# MOTHER.net
KiCad netlist of a schematic drawn in Altium Designer
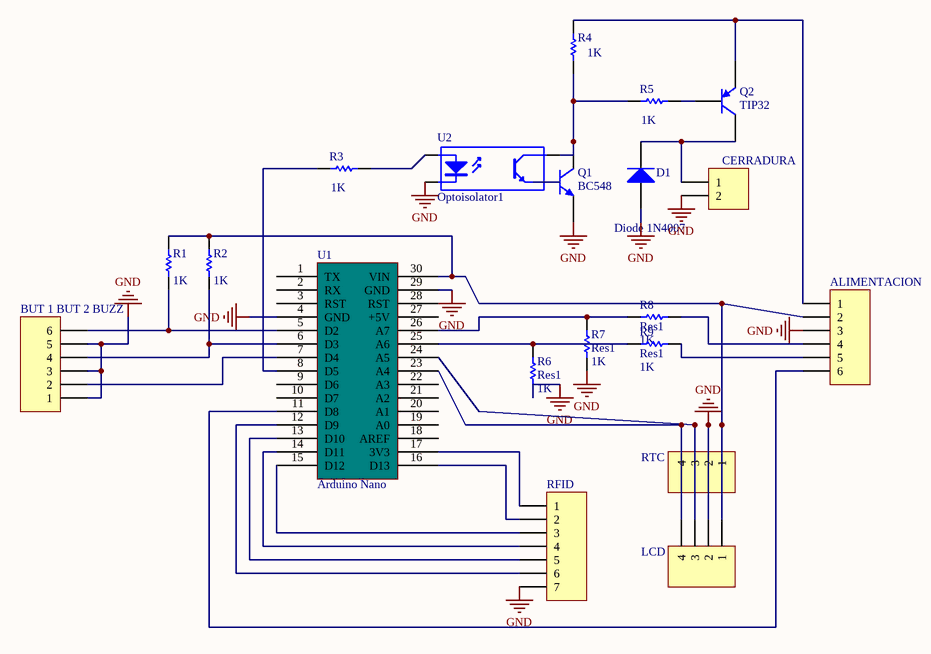
[diagram p0: MOTHER.SchDoc]

(export (version "E")
  (design (tool "Eeschema 10.0.6"))
  (components
    (comp (ref "ALIMENTACION")
      (value "Header 6")
      (footprint "BORNERA 6 PIN")
      (description "Header, 6-Pin")
      (fields (field (name "PUBLISHER") "Altium Limited"))
      (libsource (lib "") (part "Header 6_1"))
    )
    (comp (ref "BUT 1 BUT 2 BUZZ")
      (value "Header 6")
      (footprint "BORNERA 6 PIN")
      (description "Header, 6-Pin")
      (fields (field (name "PUBLISHER") "Altium Limited"))
      (libsource (lib "Miscellaneous Connectors") (part "Header 6"))
    )
    (comp (ref "CERRADURA")
      (value "Header 2")
      (footprint "Bornera 2 pin")
      (description "Header, 2-Pin")
      (fields (field (name "PUBLISHER") "Altium Limited"))
      (libsource (lib "Miscellaneous Connectors") (part "Header 2"))
    )
    (comp (ref "D1")
      (value "Diode 1N4007")
      (footprint "DO-41")
      (description "1 Amp General Purpose Rectifier")
      (fields (field (name "PUBLISHER") "Altium Limited"))
      (libsource (lib "Miscellaneous Devices") (part "Diode 1N4007"))
    )
    (comp (ref "LCD")
      (value "Header 4")
      (footprint "BORNERA 4 PIN")
      (description "Header, 4-Pin")
      (fields (field (name "PUBLISHER") "Altium Limited"))
      (libsource (lib "Miscellaneous Connectors") (part "Header 4"))
    )
    (comp (ref "Q1")
      (value "BC548")
      (footprint "TO-92A")
      (description "NPN General Purpose Amplifier")
      (fields (field (name "PUBLISHER") "Altium Limited"))
      (libsource (lib "Miscellaneous Devices") (part "2N3904"))
    )
    (comp (ref "Q2")
      (value "TIP32")
      (footprint "TO-220AB")
      (description "PNP General Purpose Amplifier")
      (fields (field (name "PUBLISHER") "Altium Limited"))
      (libsource (lib "Miscellaneous Devices") (part "2N3906"))
    )
    (comp (ref "R1")
      (value "1K")
      (footprint "AXIAL-0.3")
      (description "Resistor")
      (fields (field (name "Comment") "Res1") (field (name "PUBLISHER") "Altium Limited"))
      (libsource (lib "Miscellaneous Devices") (part "Res1"))
    )
    (comp (ref "R2")
      (value "1K")
      (footprint "AXIAL-0.3")
      (description "Resistor")
      (fields (field (name "Comment") "Res1") (field (name "PUBLISHER") "Altium Limited"))
      (libsource (lib "Miscellaneous Devices") (part "Res1"))
    )
    (comp (ref "R3")
      (value "1K")
      (footprint "AXIAL-0.3")
      (description "Resistor")
      (fields (field (name "Comment") "Res1") (field (name "PUBLISHER") "Altium Limited"))
      (libsource (lib "Miscellaneous Devices") (part "Res1"))
    )
    (comp (ref "R4")
      (value "1K")
      (footprint "AXIAL-0.3")
      (description "Resistor")
      (fields (field (name "Comment") "Res1") (field (name "PUBLISHER") "Altium Limited"))
      (libsource (lib "Miscellaneous Devices") (part "Res1"))
    )
    (comp (ref "R5")
      (value "1K")
      (footprint "AXIAL-0.3")
      (description "Resistor")
      (fields (field (name "Comment") "Res1") (field (name "PUBLISHER") "Altium Limited"))
      (libsource (lib "Miscellaneous Devices") (part "Res1"))
    )
    (comp (ref "R6")
      (value "Res1")
      (footprint "AXIAL-0.3")
      (description "Resistor")
      (fields (field (name "ALTIUM_VALUE") "1K") (field (name "PUBLISHER") "Altium Limited"))
      (libsource (lib "Miscellaneous Devices") (part "Res1"))
    )
    (comp (ref "R7")
      (value "Res1")
      (footprint "AXIAL-0.3")
      (description "Resistor")
      (fields (field (name "ALTIUM_VALUE") "1K") (field (name "PUBLISHER") "Altium Limited"))
      (libsource (lib "Miscellaneous Devices") (part "Res1"))
    )
    (comp (ref "R8")
      (value "Res1")
      (footprint "AXIAL-0.3")
      (description "Resistor")
      (fields (field (name "ALTIUM_VALUE") "1K") (field (name "PUBLISHER") "Altium Limited"))
      (libsource (lib "Miscellaneous Devices") (part "Res1"))
    )
    (comp (ref "R9")
      (value "Res1")
      (footprint "AXIAL-0.3")
      (description "Resistor")
      (fields (field (name "ALTIUM_VALUE") "1K") (field (name "PUBLISHER") "Altium Limited"))
      (libsource (lib "Miscellaneous Devices") (part "Res1"))
    )
    (comp (ref "RFID")
      (value "Header 7")
      (footprint "BORNERA 7 PIN")
      (description "Header, 7-Pin")
      (fields (field (name "PUBLISHER") "Altium Limited"))
      (libsource (lib "Miscellaneous Connectors") (part "Header 7"))
    )
    (comp (ref "RTC")
      (value "Header 4")
      (footprint "BORNERA 4 PIN")
      (description "Header, 4-Pin")
      (fields (field (name "PUBLISHER") "Altium Limited"))
      (libsource (lib "Miscellaneous Connectors") (part "Header 4"))
    )
    (comp (ref "U1")
      (value "Arduino Nano")
      (footprint "Arduino nano")
      (libsource (lib "Nano") (part "Component_1"))
    )
    (comp (ref "U2")
      (value "Optoisolator1")
      (footprint "DIP-6")
      (description "4-Pin Phototransistor Optocoupler")
      (fields (field (name "PUBLISHER") "Altium Limited"))
      (libsource (lib "Miscellaneous Devices") (part "Optoisolator1"))
    )
  )
  (nets
    (net (code "1") (name "GND") (class "Default")
      (node (ref "ALIMENTACION") (pin "3") (pinfunction "3_3") (pintype "passive"))
      (node (ref "BUT 1 BUT 2 BUZZ") (pin "1") (pinfunction "1_1") (pintype "passive"))
      (node (ref "BUT 1 BUT 2 BUZZ") (pin "3") (pinfunction "3_3") (pintype "passive"))
      (node (ref "BUT 1 BUT 2 BUZZ") (pin "5") (pinfunction "5_5") (pintype "passive"))
      (node (ref "CERRADURA") (pin "2") (pinfunction "2_2") (pintype "passive"))
      (node (ref "D1") (pin "1") (pinfunction "A_1") (pintype "passive"))
      (node (ref "LCD") (pin "2") (pinfunction "2_2") (pintype "passive"))
      (node (ref "Q1") (pin "1") (pinfunction "E_1") (pintype "passive"))
      (node (ref "R6") (pin "1") (pinfunction "1_1") (pintype "passive"))
      (node (ref "R7") (pin "1") (pinfunction "1_1") (pintype "passive"))
      (node (ref "RFID") (pin "7") (pinfunction "7_7") (pintype "passive"))
      (node (ref "RTC") (pin "2") (pinfunction "2_2") (pintype "passive"))
      (node (ref "U1") (pin "29") (pinfunction "GND_29") (pintype "passive"))
      (node (ref "U1") (pin "4") (pinfunction "GND_4") (pintype "passive"))
      (node (ref "U2") (pin "2") (pinfunction "K_2") (pintype "passive"))
    )
    (net (code "2") (name "Net-(ALIMENTACION-Pad4)") (class "Default")
      (node (ref "ALIMENTACION") (pin "4") (pinfunction "4_4") (pintype "passive"))
      (node (ref "R8") (pin "2") (pinfunction "2_2") (pintype "passive"))
    )
    (net (code "3") (name "Net-(ALIMENTACION-Pad5)") (class "Default")
      (node (ref "ALIMENTACION") (pin "5") (pinfunction "5_5") (pintype "passive"))
      (node (ref "R9") (pin "2") (pinfunction "2_2") (pintype "passive"))
    )
    (net (code "4") (name "Net-(D1-K)") (class "Default")
      (node (ref "CERRADURA") (pin "1") (pinfunction "1_1") (pintype "passive"))
      (node (ref "D1") (pin "2") (pinfunction "K_2") (pintype "passive"))
      (node (ref "Q2") (pin "3") (pinfunction "C_3") (pintype "passive"))
    )
    (net (code "5") (name "Net-(Q1-B)") (class "Default")
      (node (ref "Q1") (pin "2") (pinfunction "B_2") (pintype "passive"))
      (node (ref "U2") (pin "3") (pinfunction "E_3") (pintype "passive"))
    )
    (net (code "6") (name "Net-(Q1-C)") (class "Default")
      (node (ref "Q1") (pin "3") (pinfunction "C_3") (pintype "passive"))
      (node (ref "R4") (pin "1") (pinfunction "1_1") (pintype "passive"))
      (node (ref "R5") (pin "1") (pinfunction "1_1") (pintype "passive"))
      (node (ref "U2") (pin "4") (pinfunction "C_4") (pintype "passive"))
    )
    (net (code "7") (name "Net-(Q2-B)") (class "Default")
      (node (ref "Q2") (pin "2") (pinfunction "B_2") (pintype "passive"))
      (node (ref "R5") (pin "2") (pinfunction "2_2") (pintype "passive"))
    )
    (net (code "8") (name "Net-(Q2-E)") (class "Default")
      (node (ref "ALIMENTACION") (pin "1") (pinfunction "1_1") (pintype "passive"))
      (node (ref "Q2") (pin "1") (pinfunction "E_1") (pintype "passive"))
      (node (ref "R4") (pin "2") (pinfunction "2_2") (pintype "passive"))
    )
    (net (code "9") (name "Net-(U1-3V3)") (class "Default")
      (node (ref "RFID") (pin "1") (pinfunction "1_1") (pintype "passive"))
      (node (ref "U1") (pin "17") (pinfunction "3V3_17") (pintype "passive"))
    )
    (net (code "10") (name "Net-(U1-A4)") (class "Default")
      (node (ref "LCD") (pin "4") (pinfunction "4_4") (pintype "passive"))
      (node (ref "RTC") (pin "4") (pinfunction "4_4") (pintype "passive"))
      (node (ref "U1") (pin "23") (pinfunction "A4_23") (pintype "passive"))
    )
    (net (code "11") (name "Net-(U1-A5)") (class "Default")
      (node (ref "LCD") (pin "3") (pinfunction "3_3") (pintype "passive"))
      (node (ref "RTC") (pin "3") (pinfunction "3_3") (pintype "passive"))
      (node (ref "U1") (pin "24") (pinfunction "A5_24") (pintype "passive"))
    )
    (net (code "12") (name "Net-(U1-A6)") (class "Default")
      (node (ref "R6") (pin "2") (pinfunction "2_2") (pintype "passive"))
      (node (ref "R9") (pin "1") (pinfunction "1_1") (pintype "passive"))
      (node (ref "U1") (pin "25") (pinfunction "A6_25") (pintype "passive"))
    )
    (net (code "13") (name "Net-(U1-A7)") (class "Default")
      (node (ref "R7") (pin "2") (pinfunction "2_2") (pintype "passive"))
      (node (ref "R8") (pin "1") (pinfunction "1_1") (pintype "passive"))
      (node (ref "U1") (pin "26") (pinfunction "A7_26") (pintype "passive"))
    )
    (net (code "14") (name "Net-(U1-D2)") (class "Default")
      (node (ref "BUT 1 BUT 2 BUZZ") (pin "6") (pinfunction "6_6") (pintype "passive"))
      (node (ref "R1") (pin "1") (pinfunction "1_1") (pintype "passive"))
      (node (ref "U1") (pin "5") (pinfunction "D2_5") (pintype "passive"))
    )
    (net (code "15") (name "Net-(U1-D3)") (class "Default")
      (node (ref "BUT 1 BUT 2 BUZZ") (pin "4") (pinfunction "4_4") (pintype "passive"))
      (node (ref "R2") (pin "1") (pinfunction "1_1") (pintype "passive"))
      (node (ref "U1") (pin "6") (pinfunction "D3_6") (pintype "passive"))
    )
    (net (code "16") (name "Net-(U1-D4)") (class "Default")
      (node (ref "BUT 1 BUT 2 BUZZ") (pin "2") (pinfunction "2_2") (pintype "passive"))
      (node (ref "U1") (pin "7") (pinfunction "D4_7") (pintype "passive"))
    )
    (net (code "17") (name "Net-(U1-D5)") (class "Default")
      (node (ref "R3") (pin "1") (pinfunction "1_1") (pintype "passive"))
      (node (ref "U1") (pin "8") (pinfunction "D5_8") (pintype "passive"))
    )
    (net (code "18") (name "Net-(U1-D8)") (class "Default")
      (node (ref "ALIMENTACION") (pin "6") (pinfunction "6_6") (pintype "passive"))
      (node (ref "U1") (pin "11") (pinfunction "D8_11") (pintype "passive"))
    )
    (net (code "19") (name "Net-(U1-D9)") (class "Default")
      (node (ref "RFID") (pin "6") (pinfunction "6_6") (pintype "passive"))
      (node (ref "U1") (pin "12") (pinfunction "D9_12") (pintype "passive"))
    )
    (net (code "20") (name "Net-(U1-D10)") (class "Default")
      (node (ref "RFID") (pin "5") (pinfunction "5_5") (pintype "passive"))
      (node (ref "U1") (pin "13") (pinfunction "D10_13") (pintype "passive"))
    )
    (net (code "21") (name "Net-(U1-D11)") (class "Default")
      (node (ref "RFID") (pin "4") (pinfunction "4_4") (pintype "passive"))
      (node (ref "U1") (pin "14") (pinfunction "D11_14") (pintype "passive"))
    )
    (net (code "22") (name "Net-(U1-D12)") (class "Default")
      (node (ref "RFID") (pin "3") (pinfunction "3_3") (pintype "passive"))
      (node (ref "U1") (pin "15") (pinfunction "D12_15") (pintype "passive"))
    )
    (net (code "23") (name "Net-(U1-D13)") (class "Default")
      (node (ref "RFID") (pin "2") (pinfunction "2_2") (pintype "passive"))
      (node (ref "U1") (pin "16") (pinfunction "D13_16") (pintype "passive"))
    )
    (net (code "24") (name "Net-(U1-VIN)") (class "Default")
      (node (ref "ALIMENTACION") (pin "2") (pinfunction "2_2") (pintype "passive"))
      (node (ref "LCD") (pin "1") (pinfunction "1_1") (pintype "passive"))
      (node (ref "R1") (pin "2") (pinfunction "2_2") (pintype "passive"))
      (node (ref "R2") (pin "2") (pinfunction "2_2") (pintype "passive"))
      (node (ref "RTC") (pin "1") (pinfunction "1_1") (pintype "passive"))
      (node (ref "U1") (pin "30") (pinfunction "VIN_30") (pintype "passive"))
    )
    (net (code "25") (name "Net-(U2-A)") (class "Default")
      (node (ref "R3") (pin "2") (pinfunction "2_2") (pintype "passive"))
      (node (ref "U2") (pin "1") (pinfunction "A_1") (pintype "passive"))
    )
    (net (code "26") (name "unconnected-(U1-+5V-Pad27)") (class "Default")
      (node (ref "U1") (pin "27") (pinfunction "+5V_27") (pintype "passive"))
    )
    (net (code "27") (name "unconnected-(U1-A0-Pad19)") (class "Default")
      (node (ref "U1") (pin "19") (pinfunction "A0_19") (pintype "passive"))
    )
    (net (code "28") (name "unconnected-(U1-A1-Pad20)") (class "Default")
      (node (ref "U1") (pin "20") (pinfunction "A1_20") (pintype "passive"))
    )
    (net (code "29") (name "unconnected-(U1-A2-Pad21)") (class "Default")
      (node (ref "U1") (pin "21") (pinfunction "A2_21") (pintype "passive"))
    )
    (net (code "30") (name "unconnected-(U1-A3-Pad22)") (class "Default")
      (node (ref "U1") (pin "22") (pinfunction "A3_22") (pintype "passive"))
    )
    (net (code "31") (name "unconnected-(U1-AREF-Pad18)") (class "Default")
      (node (ref "U1") (pin "18") (pinfunction "AREF_18") (pintype "passive"))
    )
    (net (code "32") (name "unconnected-(U1-D6-Pad9)") (class "Default")
      (node (ref "U1") (pin "9") (pinfunction "D6_9") (pintype "passive"))
    )
    (net (code "33") (name "unconnected-(U1-D7-Pad10)") (class "Default")
      (node (ref "U1") (pin "10") (pinfunction "D7_10") (pintype "passive"))
    )
    (net (code "34") (name "unconnected-(U1-RST-Pad3)") (class "Default")
      (node (ref "U1") (pin "3") (pinfunction "RST_3") (pintype "passive"))
    )
    (net (code "35") (name "unconnected-(U1-RST-Pad28)") (class "Default")
      (node (ref "U1") (pin "28") (pinfunction "RST_28") (pintype "passive"))
    )
    (net (code "36") (name "unconnected-(U1-RX-Pad2)") (class "Default")
      (node (ref "U1") (pin "2") (pinfunction "RX_2") (pintype "passive"))
    )
    (net (code "37") (name "unconnected-(U1-TX-Pad1)") (class "Default")
      (node (ref "U1") (pin "1") (pinfunction "TX_1") (pintype "passive"))
    )
  )
)
